# xtend_breakout.net
KiCad netlist of a schematic drawn in EAGLE
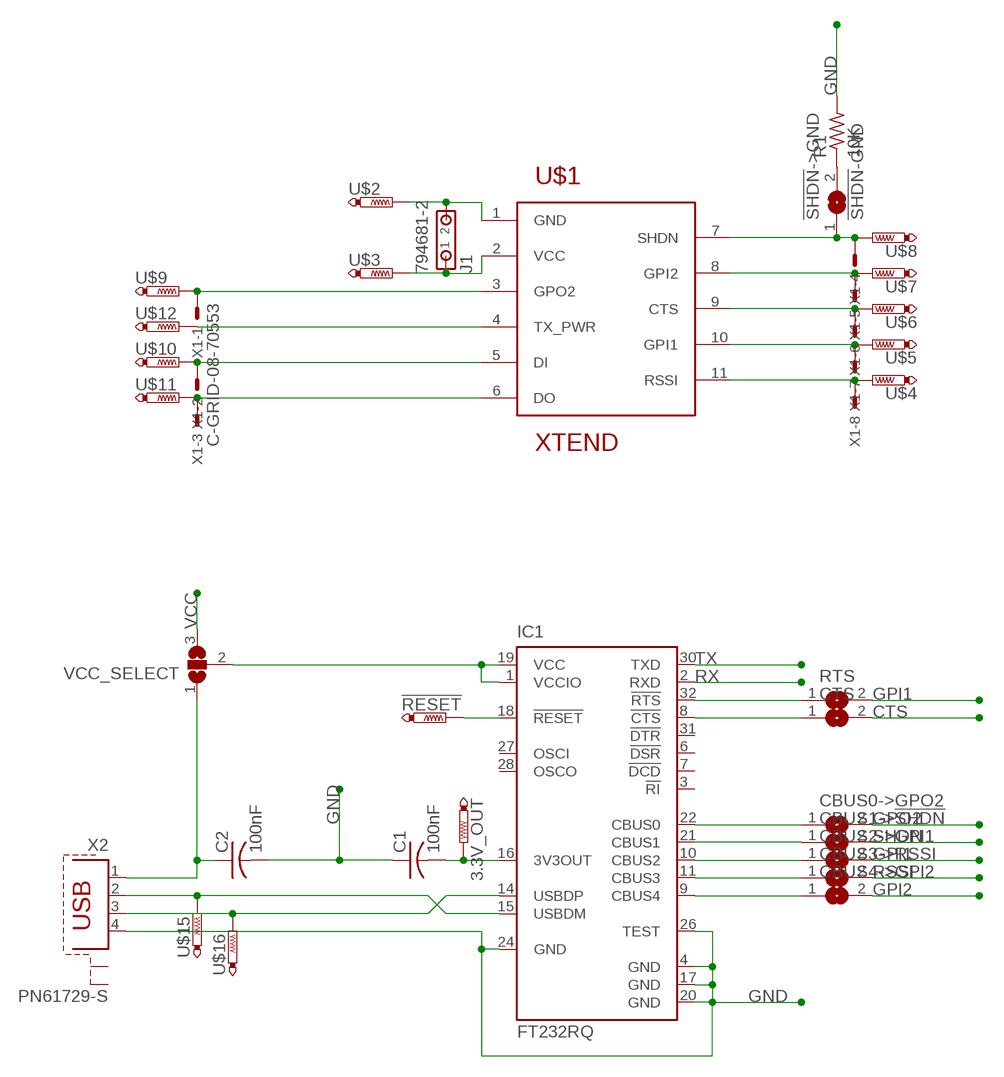
[diagram p0: schematic, sheet 1]

(export (version "E")
  (design (tool "Eeschema 10.0.6"))
  (components
    (comp (ref "!RESET!")
      (value "TESTPAD-20MIL")
      (footprint "eagle-import:20MIL")
      (libsource (lib "eagle-import") (part "TESTPAD-20MIL"))
    )
    (comp (ref "!SHDN!->GND")
      (value "!SHDN!-GND")
      (footprint "eagle-import:SJ")
      (libsource (lib "eagle-import") (part "SJ"))
    )
    (comp (ref "3.3V_OUT")
      (value "TESTPAD-20MIL")
      (footprint "eagle-import:20MIL")
      (libsource (lib "eagle-import") (part "TESTPAD-20MIL"))
    )
    (comp (ref "C1")
      (value "100nF")
      (footprint "eagle-import:C1206")
      (libsource (lib "eagle-import") (part "C-USC1206"))
    )
    (comp (ref "C2")
      (value "100nF")
      (footprint "eagle-import:C1206")
      (libsource (lib "eagle-import") (part "C-USC1206"))
    )
    (comp (ref "CBUS0->GPO2")
      (value "SJ")
      (footprint "eagle-import:SJ")
      (libsource (lib "eagle-import") (part "SJ"))
    )
    (comp (ref "CBUS1->!SHDN!")
      (value "SJ")
      (footprint "eagle-import:SJ")
      (libsource (lib "eagle-import") (part "SJ"))
    )
    (comp (ref "CBUS2->GPI1")
      (value "SJ")
      (footprint "eagle-import:SJ")
      (libsource (lib "eagle-import") (part "SJ"))
    )
    (comp (ref "CBUS3->RSSI")
      (value "SJ")
      (footprint "eagle-import:SJ")
      (libsource (lib "eagle-import") (part "SJ"))
    )
    (comp (ref "CBUS4->GPI2")
      (value "SJ")
      (footprint "eagle-import:SJ")
      (libsource (lib "eagle-import") (part "SJ"))
    )
    (comp (ref "CTS") (value "SJ") (footprint "eagle-import:SJ") (libsource (lib "eagle-import") (part "SJ")))
    (comp (ref "IC1")
      (value "FT232RQ")
      (footprint "eagle-import:QFN32")
      (libsource (lib "eagle-import") (part "FT232RQ"))
    )
    (comp (ref "J1")
      (value "794681-2")
      (footprint "eagle-import:794681-2")
      (libsource (lib "eagle-import") (part "794681-2"))
    )
    (comp (ref "R1")
      (value "10K")
      (footprint "eagle-import:R1206")
      (libsource (lib "eagle-import") (part "R-US_R1206"))
    )
    (comp (ref "RTS") (value "SJ") (footprint "eagle-import:SJ") (libsource (lib "eagle-import") (part "SJ")))
    (comp (ref "U$1")
      (value "XTEND")
      (footprint "eagle-import:XTEND")
      (libsource (lib "eagle-import") (part "XTEND"))
    )
    (comp (ref "U$2")
      (value "TESTPAD-20MIL")
      (footprint "eagle-import:20MIL")
      (libsource (lib "eagle-import") (part "TESTPAD-20MIL"))
    )
    (comp (ref "U$3")
      (value "TESTPAD-20MIL")
      (footprint "eagle-import:20MIL")
      (libsource (lib "eagle-import") (part "TESTPAD-20MIL"))
    )
    (comp (ref "U$4")
      (value "TESTPAD-20MIL")
      (footprint "eagle-import:20MIL")
      (libsource (lib "eagle-import") (part "TESTPAD-20MIL"))
    )
    (comp (ref "U$5")
      (value "TESTPAD-20MIL")
      (footprint "eagle-import:20MIL")
      (libsource (lib "eagle-import") (part "TESTPAD-20MIL"))
    )
    (comp (ref "U$6")
      (value "TESTPAD-20MIL")
      (footprint "eagle-import:20MIL")
      (libsource (lib "eagle-import") (part "TESTPAD-20MIL"))
    )
    (comp (ref "U$7")
      (value "TESTPAD-20MIL")
      (footprint "eagle-import:20MIL")
      (libsource (lib "eagle-import") (part "TESTPAD-20MIL"))
    )
    (comp (ref "U$8")
      (value "TESTPAD-20MIL")
      (footprint "eagle-import:20MIL")
      (libsource (lib "eagle-import") (part "TESTPAD-20MIL"))
    )
    (comp (ref "U$9")
      (value "TESTPAD-20MIL")
      (footprint "eagle-import:20MIL")
      (libsource (lib "eagle-import") (part "TESTPAD-20MIL"))
    )
    (comp (ref "U$10")
      (value "TESTPAD-20MIL")
      (footprint "eagle-import:20MIL")
      (libsource (lib "eagle-import") (part "TESTPAD-20MIL"))
    )
    (comp (ref "U$11")
      (value "TESTPAD-20MIL")
      (footprint "eagle-import:20MIL")
      (libsource (lib "eagle-import") (part "TESTPAD-20MIL"))
    )
    (comp (ref "U$12")
      (value "TESTPAD-20MIL")
      (footprint "eagle-import:20MIL")
      (libsource (lib "eagle-import") (part "TESTPAD-20MIL"))
    )
    (comp (ref "U$15")
      (value "TESTPAD-20MIL")
      (footprint "eagle-import:20MIL")
      (libsource (lib "eagle-import") (part "TESTPAD-20MIL"))
    )
    (comp (ref "U$16")
      (value "TESTPAD-20MIL")
      (footprint "eagle-import:20MIL")
      (libsource (lib "eagle-import") (part "TESTPAD-20MIL"))
    )
    (comp (ref "VCC_SELECT")
      (value "SJ2W")
      (footprint "eagle-import:SJ_2")
      (libsource (lib "eagle-import") (part "SJ2W"))
    )
    (comp (ref "X1")
      (value "C-GRID-08-70553")
      (footprint "eagle-import:70553-08")
      (libsource (lib "eagle-import") (part "C-GRID-08-70553"))
    )
    (comp (ref "X2")
      (value "PN61729-S")
      (footprint "eagle-import:PN61729-S")
      (libsource (lib "eagle-import") (part "PN61729-S"))
    )
  )
  (nets
    (net (code "1") (name "/CTS") (class "Default")
      (node (ref "CTS") (pin "2") (pinfunction "2_2") (pintype "passive"))
      (node (ref "U$1") (pin "9") (pinfunction "CTS_9") (pintype "bidirectional"))
      (node (ref "U$6") (pin "P$1") (pinfunction "TP_P$1") (pintype "input"))
      (node (ref "X1") (pin "6") (pinfunction "S_6") (pintype "passive"))
    )
    (net (code "2") (name "/GND") (class "Default")
      (node (ref "C1") (pin "1") (pinfunction "1_1") (pintype "passive"))
      (node (ref "C2") (pin "2") (pinfunction "2_2") (pintype "passive"))
      (node (ref "IC1") (pin "17") (pinfunction "GND_17") (pintype "power_in"))
      (node (ref "IC1") (pin "20") (pinfunction "GND_20") (pintype "power_in"))
      (node (ref "IC1") (pin "24") (pinfunction "GND_24") (pintype "power_in"))
      (node (ref "IC1") (pin "26") (pinfunction "TEST_26") (pintype "input"))
      (node (ref "IC1") (pin "4") (pinfunction "GND_4") (pintype "power_in"))
      (node (ref "J1") (pin "2") (pinfunction "2_2") (pintype "passive"))
      (node (ref "R1") (pin "2") (pinfunction "2_2") (pintype "passive"))
      (node (ref "U$1") (pin "1") (pinfunction "GND_1") (pintype "bidirectional"))
      (node (ref "U$2") (pin "P$1") (pinfunction "TP_P$1") (pintype "input"))
      (node (ref "X2") (pin "4") (pinfunction "4_4") (pintype "passive"))
    )
    (net (code "3") (name "/GPI1") (class "Default")
      (node (ref "CBUS2->GPI1") (pin "2") (pinfunction "2_2") (pintype "passive"))
      (node (ref "RTS") (pin "2") (pinfunction "2_2") (pintype "passive"))
      (node (ref "U$1") (pin "10") (pinfunction "GPI1_10") (pintype "bidirectional"))
      (node (ref "U$5") (pin "P$1") (pinfunction "TP_P$1") (pintype "input"))
      (node (ref "X1") (pin "7") (pinfunction "S_7") (pintype "passive"))
    )
    (net (code "4") (name "/GPI2") (class "Default")
      (node (ref "CBUS4->GPI2") (pin "2") (pinfunction "2_2") (pintype "passive"))
      (node (ref "U$1") (pin "8") (pinfunction "GPI2_8") (pintype "bidirectional"))
      (node (ref "U$7") (pin "P$1") (pinfunction "TP_P$1") (pintype "input"))
      (node (ref "X1") (pin "5") (pinfunction "S_5") (pintype "passive"))
    )
    (net (code "5") (name "/GPO2") (class "Default")
      (node (ref "CBUS0->GPO2") (pin "2") (pinfunction "2_2") (pintype "passive"))
      (node (ref "U$1") (pin "3") (pinfunction "GPO2_3") (pintype "bidirectional"))
      (node (ref "U$9") (pin "P$1") (pinfunction "TP_P$1") (pintype "input"))
      (node (ref "X1") (pin "1") (pinfunction "S_1") (pintype "passive"))
    )
    (net (code "6") (name "/RSSI") (class "Default")
      (node (ref "CBUS3->RSSI") (pin "2") (pinfunction "2_2") (pintype "passive"))
      (node (ref "U$1") (pin "11") (pinfunction "RSSI_11") (pintype "bidirectional"))
      (node (ref "U$4") (pin "P$1") (pinfunction "TP_P$1") (pintype "input"))
      (node (ref "X1") (pin "8") (pinfunction "S_8") (pintype "passive"))
    )
    (net (code "7") (name "/RX") (class "Default")
      (node (ref "IC1") (pin "2") (pinfunction "RXD_2") (pintype "input"))
      (node (ref "U$1") (pin "6") (pinfunction "DO_6") (pintype "bidirectional"))
      (node (ref "U$11") (pin "P$1") (pinfunction "TP_P$1") (pintype "input"))
      (node (ref "X1") (pin "3") (pinfunction "S_3") (pintype "passive"))
    )
    (net (code "8") (name "/SHDN") (class "Default")
      (node (ref "!SHDN!->GND") (pin "1") (pinfunction "1_1") (pintype "passive"))
      (node (ref "CBUS1->!SHDN!") (pin "2") (pinfunction "2_2") (pintype "passive"))
      (node (ref "U$1") (pin "7") (pinfunction "SHDN_7") (pintype "bidirectional"))
      (node (ref "U$8") (pin "P$1") (pinfunction "TP_P$1") (pintype "input"))
      (node (ref "X1") (pin "4") (pinfunction "S_4") (pintype "passive"))
    )
    (net (code "9") (name "/TX") (class "Default")
      (node (ref "IC1") (pin "30") (pinfunction "TXD_30") (pintype "output"))
      (node (ref "U$1") (pin "5") (pinfunction "DI_5") (pintype "bidirectional"))
      (node (ref "U$10") (pin "P$1") (pinfunction "TP_P$1") (pintype "input"))
      (node (ref "X1") (pin "2") (pinfunction "S_2") (pintype "passive"))
    )
    (net (code "10") (name "/VCC") (class "Default")
      (node (ref "J1") (pin "1") (pinfunction "1_1") (pintype "passive"))
      (node (ref "U$1") (pin "2") (pinfunction "VCC_2") (pintype "bidirectional"))
      (node (ref "U$3") (pin "P$1") (pinfunction "TP_P$1") (pintype "input"))
      (node (ref "VCC_SELECT") (pin "3") (pinfunction "3_3") (pintype "passive"))
    )
    (net (code "11") (name "Net-(!RESET!-TP)") (class "Default")
      (node (ref "!RESET!") (pin "P$1") (pinfunction "TP_P$1") (pintype "input"))
      (node (ref "IC1") (pin "18") (pinfunction "~{RESET}_18") (pintype "input"))
    )
    (net (code "12") (name "Net-(!SHDN!->GND-Pad2)") (class "Default")
      (node (ref "!SHDN!->GND") (pin "2") (pinfunction "2_2") (pintype "passive"))
      (node (ref "R1") (pin "1") (pinfunction "1_1") (pintype "passive"))
    )
    (net (code "13") (name "Net-(3.3V_OUT-TP)") (class "Default")
      (node (ref "3.3V_OUT") (pin "P$1") (pinfunction "TP_P$1") (pintype "input"))
      (node (ref "C1") (pin "2") (pinfunction "2_2") (pintype "passive"))
      (node (ref "IC1") (pin "16") (pinfunction "3V3OUT_16") (pintype "output"))
    )
    (net (code "14") (name "Net-(C2-Pad1)") (class "Default")
      (node (ref "C2") (pin "1") (pinfunction "1_1") (pintype "passive"))
      (node (ref "VCC_SELECT") (pin "1") (pinfunction "1_1") (pintype "passive"))
      (node (ref "X2") (pin "1") (pinfunction "1_1") (pintype "passive"))
    )
    (net (code "15") (name "Net-(IC1-CBUS0)") (class "Default")
      (node (ref "CBUS0->GPO2") (pin "1") (pinfunction "1_1") (pintype "passive"))
      (node (ref "IC1") (pin "22") (pinfunction "CBUS0_22") (pintype "bidirectional"))
    )
    (net (code "16") (name "Net-(IC1-CBUS1)") (class "Default")
      (node (ref "CBUS1->!SHDN!") (pin "1") (pinfunction "1_1") (pintype "passive"))
      (node (ref "IC1") (pin "21") (pinfunction "CBUS1_21") (pintype "bidirectional"))
    )
    (net (code "17") (name "Net-(IC1-CBUS2)") (class "Default")
      (node (ref "CBUS2->GPI1") (pin "1") (pinfunction "1_1") (pintype "passive"))
      (node (ref "IC1") (pin "10") (pinfunction "CBUS2_10") (pintype "bidirectional"))
    )
    (net (code "18") (name "Net-(IC1-CBUS3)") (class "Default")
      (node (ref "CBUS3->RSSI") (pin "1") (pinfunction "1_1") (pintype "passive"))
      (node (ref "IC1") (pin "11") (pinfunction "CBUS3_11") (pintype "bidirectional"))
    )
    (net (code "19") (name "Net-(IC1-CBUS4)") (class "Default")
      (node (ref "CBUS4->GPI2") (pin "1") (pinfunction "1_1") (pintype "passive"))
      (node (ref "IC1") (pin "9") (pinfunction "CBUS4_9") (pintype "bidirectional"))
    )
    (net (code "20") (name "Net-(IC1-USBDM)") (class "Default")
      (node (ref "IC1") (pin "15") (pinfunction "USBDM_15") (pintype "bidirectional"))
      (node (ref "U$15") (pin "P$1") (pinfunction "TP_P$1") (pintype "input"))
      (node (ref "X2") (pin "2") (pinfunction "2_2") (pintype "passive"))
    )
    (net (code "21") (name "Net-(IC1-USBDP)") (class "Default")
      (node (ref "IC1") (pin "14") (pinfunction "USBDP_14") (pintype "bidirectional"))
      (node (ref "U$16") (pin "P$1") (pinfunction "TP_P$1") (pintype "input"))
      (node (ref "X2") (pin "3") (pinfunction "3_3") (pintype "passive"))
    )
    (net (code "22") (name "Net-(IC1-VCC)") (class "Default")
      (node (ref "IC1") (pin "1") (pinfunction "VCCIO_1") (pintype "power_in"))
      (node (ref "IC1") (pin "19") (pinfunction "VCC_19") (pintype "power_in"))
      (node (ref "VCC_SELECT") (pin "2") (pinfunction "2_2") (pintype "passive"))
    )
    (net (code "23") (name "Net-(IC1-~{CTS})") (class "Default")
      (node (ref "CTS") (pin "1") (pinfunction "1_1") (pintype "passive"))
      (node (ref "IC1") (pin "8") (pinfunction "~{CTS}_8") (pintype "input"))
    )
    (net (code "24") (name "Net-(IC1-~{RTS})") (class "Default")
      (node (ref "IC1") (pin "32") (pinfunction "~{RTS}_32") (pintype "output"))
      (node (ref "RTS") (pin "1") (pinfunction "1_1") (pintype "passive"))
    )
    (net (code "25") (name "Net-(U$1-TX_PWR)") (class "Default")
      (node (ref "U$1") (pin "4") (pinfunction "TX_PWR_4") (pintype "bidirectional"))
      (node (ref "U$12") (pin "P$1") (pinfunction "TP_P$1") (pintype "input"))
    )
    (net (code "26") (name "unconnected-(IC1-OSCI-Pad27)") (class "Default")
      (node (ref "IC1") (pin "27") (pinfunction "OSCI_27") (pintype "input"))
    )
    (net (code "27") (name "unconnected-(IC1-OSCO-Pad28)") (class "Default")
      (node (ref "IC1") (pin "28") (pinfunction "OSCO_28") (pintype "output"))
    )
    (net (code "28") (name "unconnected-(IC1-~{DCD}-Pad7)") (class "Default")
      (node (ref "IC1") (pin "7") (pinfunction "~{DCD}_7") (pintype "input"))
    )
    (net (code "29") (name "unconnected-(IC1-~{DSR}-Pad6)") (class "Default")
      (node (ref "IC1") (pin "6") (pinfunction "~{DSR}_6") (pintype "input"))
    )
    (net (code "30") (name "unconnected-(IC1-~{DTR}-Pad31)") (class "Default")
      (node (ref "IC1") (pin "31") (pinfunction "~{DTR}_31") (pintype "output"))
    )
    (net (code "31") (name "unconnected-(IC1-~{RI}-Pad3)") (class "Default")
      (node (ref "IC1") (pin "3") (pinfunction "~{RI}_3") (pintype "input"))
    )
    (net (code "32") (name "unconnected-(X2-PadS1)") (class "Default")
      (node (ref "X2") (pin "S1") (pinfunction "S1_S1") (pintype "passive"))
    )
    (net (code "33") (name "unconnected-(X2-PadS2)") (class "Default")
      (node (ref "X2") (pin "S2") (pinfunction "S2_S2") (pintype "passive"))
    )
  )
)
